# Craft.net
KiCad netlist of a schematic drawn in EAGLE
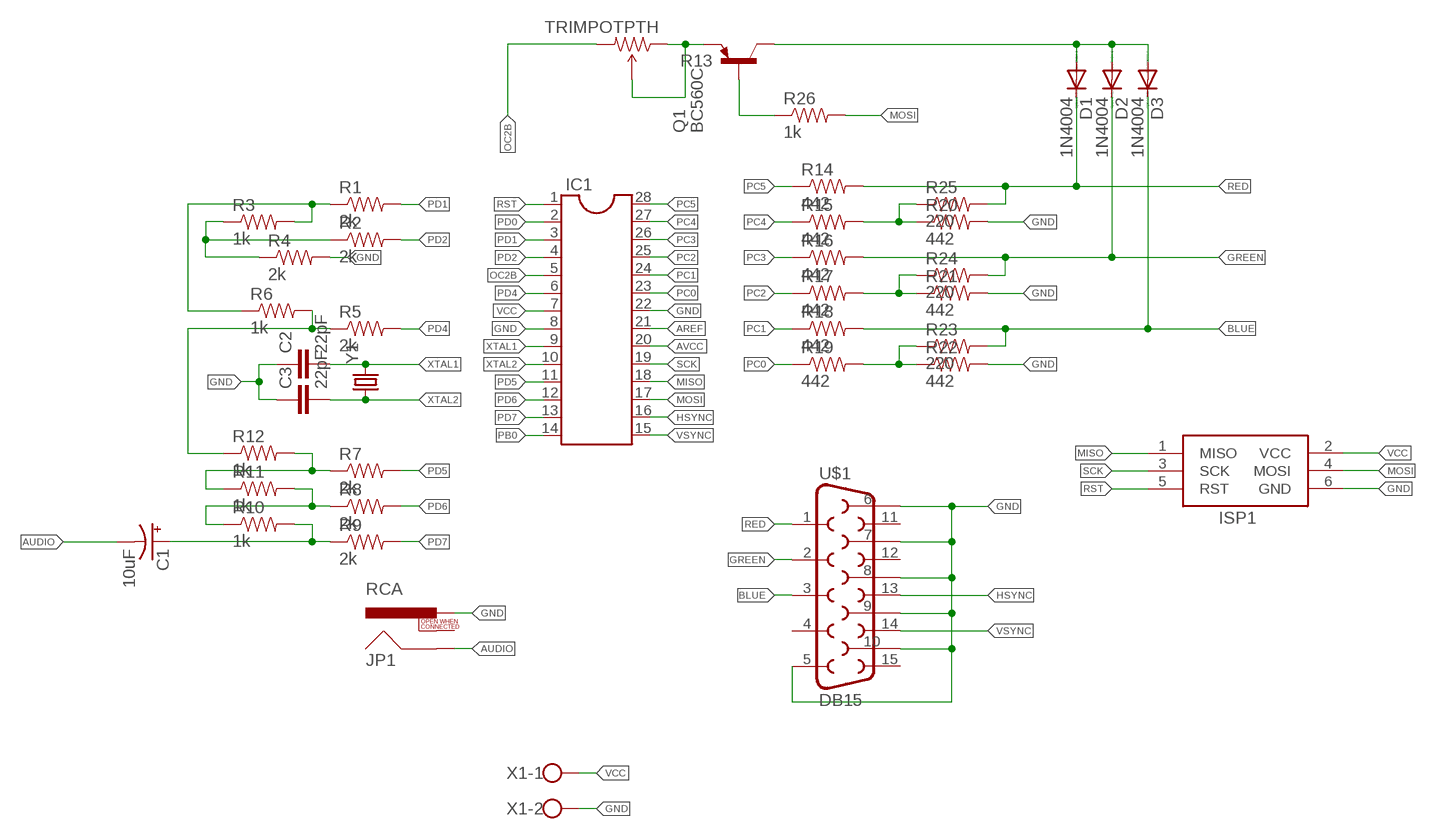
[diagram p0: schematic, sheet 1]

(export (version "E")
  (design (tool "Eeschema 10.0.6"))
  (components
    (comp (ref "C1")
      (value "10uF")
      (footprint "eagle-import:CPOL-RADIAL-100UF-25V")
      (libsource (lib "eagle-import") (part "CAP_POLPTH1"))
    )
    (comp (ref "C2")
      (value "22pF")
      (footprint "eagle-import:CAP-PTH-SMALLEZ")
      (libsource (lib "eagle-import") (part "CAPEZ"))
    )
    (comp (ref "C3")
      (value "22pF")
      (footprint "eagle-import:CAP-PTH-SMALLEZ")
      (libsource (lib "eagle-import") (part "CAPEZ"))
    )
    (comp (ref "D1")
      (value "1N4004")
      (footprint "eagle-import:DO41-10")
      (libsource (lib "eagle-import") (part "1N4004"))
    )
    (comp (ref "D2")
      (value "1N4004")
      (footprint "eagle-import:DO41-10")
      (libsource (lib "eagle-import") (part "1N4004"))
    )
    (comp (ref "D3")
      (value "1N4004")
      (footprint "eagle-import:DO41-10")
      (libsource (lib "eagle-import") (part "1N4004"))
    )
    (comp (ref "IC1")
      (value "DIL28-3")
      (footprint "eagle-import:DIL28-3")
      (libsource (lib "eagle-import") (part "DIL28-3"))
    )
    (comp (ref "ISP1")
      (value "AVRISP-6")
      (footprint "eagle-import:AVRISP")
      (libsource (lib "eagle-import") (part "AVRISP-6"))
    )
    (comp (ref "JP1")
      (value "RCA")
      (footprint "eagle-import:RCA")
      (libsource (lib "eagle-import") (part "RCA"))
    )
    (comp (ref "Q1")
      (value "BC560C")
      (footprint "eagle-import:TO92-EBC")
      (libsource (lib "eagle-import") (part "BC560C"))
    )
    (comp (ref "R1")
      (value "2k")
      (footprint "eagle-import:AXIAL-0.4")
      (libsource (lib "eagle-import") (part "RESISTORPTH-1/4W"))
    )
    (comp (ref "R2")
      (value "2k")
      (footprint "eagle-import:AXIAL-0.4")
      (libsource (lib "eagle-import") (part "RESISTORPTH-1/4W"))
    )
    (comp (ref "R3")
      (value "1k")
      (footprint "eagle-import:AXIAL-0.4")
      (libsource (lib "eagle-import") (part "RESISTORPTH-1/4W"))
    )
    (comp (ref "R4")
      (value "2k")
      (footprint "eagle-import:AXIAL-0.4")
      (libsource (lib "eagle-import") (part "RESISTORPTH-1/4W"))
    )
    (comp (ref "R5")
      (value "2k")
      (footprint "eagle-import:AXIAL-0.4")
      (libsource (lib "eagle-import") (part "RESISTORPTH-1/4W"))
    )
    (comp (ref "R6")
      (value "1k")
      (footprint "eagle-import:AXIAL-0.4")
      (libsource (lib "eagle-import") (part "RESISTORPTH-1/4W"))
    )
    (comp (ref "R7")
      (value "2k")
      (footprint "eagle-import:AXIAL-0.4")
      (libsource (lib "eagle-import") (part "RESISTORPTH-1/4W"))
    )
    (comp (ref "R8")
      (value "2k")
      (footprint "eagle-import:AXIAL-0.4")
      (libsource (lib "eagle-import") (part "RESISTORPTH-1/4W"))
    )
    (comp (ref "R9")
      (value "2k")
      (footprint "eagle-import:AXIAL-0.4")
      (libsource (lib "eagle-import") (part "RESISTORPTH-1/4W"))
    )
    (comp (ref "R10")
      (value "1k")
      (footprint "eagle-import:AXIAL-0.4")
      (libsource (lib "eagle-import") (part "RESISTORPTH-1/4W"))
    )
    (comp (ref "R11")
      (value "1k")
      (footprint "eagle-import:AXIAL-0.4")
      (libsource (lib "eagle-import") (part "RESISTORPTH-1/4W"))
    )
    (comp (ref "R12")
      (value "1k")
      (footprint "eagle-import:AXIAL-0.4")
      (libsource (lib "eagle-import") (part "RESISTORPTH-1/4W"))
    )
    (comp (ref "R13")
      (value "TRIMPOTPTH")
      (footprint "eagle-import:TRIM_POT_PTH")
      (libsource (lib "eagle-import") (part "TRIMPOTPTH"))
    )
    (comp (ref "R14")
      (value "442")
      (footprint "eagle-import:AXIAL-0.4")
      (libsource (lib "eagle-import") (part "RESISTORPTH-1/4W"))
    )
    (comp (ref "R15")
      (value "442")
      (footprint "eagle-import:AXIAL-0.4")
      (libsource (lib "eagle-import") (part "RESISTORPTH-1/4W"))
    )
    (comp (ref "R16")
      (value "442")
      (footprint "eagle-import:AXIAL-0.4")
      (libsource (lib "eagle-import") (part "RESISTORPTH-1/4W"))
    )
    (comp (ref "R17")
      (value "442")
      (footprint "eagle-import:AXIAL-0.4")
      (libsource (lib "eagle-import") (part "RESISTORPTH-1/4W"))
    )
    (comp (ref "R18")
      (value "442")
      (footprint "eagle-import:AXIAL-0.4")
      (libsource (lib "eagle-import") (part "RESISTORPTH-1/4W"))
    )
    (comp (ref "R19")
      (value "442")
      (footprint "eagle-import:AXIAL-0.4")
      (libsource (lib "eagle-import") (part "RESISTORPTH-1/4W"))
    )
    (comp (ref "R20")
      (value "442")
      (footprint "eagle-import:AXIAL-0.4")
      (libsource (lib "eagle-import") (part "RESISTORPTH-1/4W"))
    )
    (comp (ref "R21")
      (value "442")
      (footprint "eagle-import:AXIAL-0.4")
      (libsource (lib "eagle-import") (part "RESISTORPTH-1/4W"))
    )
    (comp (ref "R22")
      (value "442")
      (footprint "eagle-import:AXIAL-0.4")
      (libsource (lib "eagle-import") (part "RESISTORPTH-1/4W"))
    )
    (comp (ref "R23")
      (value "220")
      (footprint "eagle-import:AXIAL-0.4")
      (libsource (lib "eagle-import") (part "RESISTORPTH-1/4W"))
    )
    (comp (ref "R24")
      (value "220")
      (footprint "eagle-import:AXIAL-0.4")
      (libsource (lib "eagle-import") (part "RESISTORPTH-1/4W"))
    )
    (comp (ref "R25")
      (value "220")
      (footprint "eagle-import:AXIAL-0.4")
      (libsource (lib "eagle-import") (part "RESISTORPTH-1/4W"))
    )
    (comp (ref "R26")
      (value "1k")
      (footprint "eagle-import:AXIAL-0.4")
      (libsource (lib "eagle-import") (part "RESISTORPTH-1/4W"))
    )
    (comp (ref "U$1")
      (value "DB15")
      (footprint "eagle-import:DB15")
      (libsource (lib "eagle-import") (part "DB15"))
    )
    (comp (ref "X1")
      (value "W237-102")
      (footprint "eagle-import:W237-102")
      (fields (field (name "MPN") "237-102"))
      (libsource (lib "eagle-import") (part "W237-102"))
    )
    (comp (ref "Y1")
      (value "CRYSTALHC49UV")
      (footprint "eagle-import:HC49U-V")
      (libsource (lib "eagle-import") (part "CRYSTALHC49UV"))
    )
  )
  (nets
    (net (code "1") (name "AREF") (class "Default")
      (node (ref "IC1") (pin "21") (pinfunction "21_21") (pintype "passive"))
    )
    (net (code "2") (name "AUDIO") (class "Default")
      (node (ref "C1") (pin "2") (pinfunction "-_2") (pintype "passive"))
      (node (ref "JP1") (pin "SHELL") (pinfunction "SHELL_SHELL") (pintype "bidirectional"))
    )
    (net (code "3") (name "AVCC") (class "Default")
      (node (ref "IC1") (pin "20") (pinfunction "20_20") (pintype "passive"))
    )
    (net (code "4") (name "BLUE") (class "Default")
      (node (ref "D3") (pin "C") (pinfunction "C_C") (pintype "passive"))
      (node (ref "R18") (pin "P$2") (pinfunction "2_P$2") (pintype "passive"))
      (node (ref "R23") (pin "P$2") (pinfunction "2_P$2") (pintype "passive"))
      (node (ref "U$1") (pin "3") (pinfunction "3_3") (pintype "passive"))
    )
    (net (code "5") (name "GND") (class "Default")
      (node (ref "C2") (pin "1") (pinfunction "1_1") (pintype "passive"))
      (node (ref "C3") (pin "1") (pinfunction "1_1") (pintype "passive"))
      (node (ref "IC1") (pin "22") (pinfunction "22_22") (pintype "passive"))
      (node (ref "IC1") (pin "8") (pinfunction "8_8") (pintype "passive"))
      (node (ref "ISP1") (pin "6") (pinfunction "GND_6") (pintype "power_in"))
      (node (ref "JP1") (pin "PIN") (pinfunction "PIN_PIN") (pintype "bidirectional"))
      (node (ref "R20") (pin "P$2") (pinfunction "2_P$2") (pintype "passive"))
      (node (ref "R21") (pin "P$2") (pinfunction "2_P$2") (pintype "passive"))
      (node (ref "R22") (pin "P$2") (pinfunction "2_P$2") (pintype "passive"))
      (node (ref "R4") (pin "P$2") (pinfunction "2_P$2") (pintype "passive"))
      (node (ref "U$1") (pin "10") (pinfunction "10_10") (pintype "passive"))
      (node (ref "U$1") (pin "5") (pinfunction "5_5") (pintype "passive"))
      (node (ref "U$1") (pin "6") (pinfunction "6_6") (pintype "passive"))
      (node (ref "U$1") (pin "7") (pinfunction "7_7") (pintype "passive"))
      (node (ref "U$1") (pin "8") (pinfunction "8_8") (pintype "passive"))
      (node (ref "U$1") (pin "9") (pinfunction "9_9") (pintype "passive"))
      (node (ref "X1") (pin "2") (pinfunction "KL_2") (pintype "passive"))
    )
    (net (code "6") (name "GREEN") (class "Default")
      (node (ref "D2") (pin "C") (pinfunction "C_C") (pintype "passive"))
      (node (ref "R16") (pin "P$2") (pinfunction "2_P$2") (pintype "passive"))
      (node (ref "R24") (pin "P$2") (pinfunction "2_P$2") (pintype "passive"))
      (node (ref "U$1") (pin "2") (pinfunction "2_2") (pintype "passive"))
    )
    (net (code "7") (name "HSYNC") (class "Default")
      (node (ref "IC1") (pin "16") (pinfunction "16_16") (pintype "passive"))
      (node (ref "U$1") (pin "13") (pinfunction "13_13") (pintype "passive"))
    )
    (net (code "8") (name "MISO") (class "Default")
      (node (ref "IC1") (pin "18") (pinfunction "18_18") (pintype "passive"))
      (node (ref "ISP1") (pin "1") (pinfunction "MISO_1") (pintype "input"))
    )
    (net (code "9") (name "MOSI") (class "Default")
      (node (ref "IC1") (pin "17") (pinfunction "17_17") (pintype "passive"))
      (node (ref "ISP1") (pin "4") (pinfunction "MOSI_4") (pintype "output"))
      (node (ref "R26") (pin "P$2") (pinfunction "2_P$2") (pintype "passive"))
    )
    (net (code "10") (name "Net-(C1-+)") (class "Default")
      (node (ref "C1") (pin "1") (pinfunction "+_1") (pintype "passive"))
      (node (ref "R10") (pin "P$2") (pinfunction "2_P$2") (pintype "passive"))
      (node (ref "R9") (pin "P$1") (pinfunction "1_P$1") (pintype "passive"))
    )
    (net (code "11") (name "Net-(D1-PadA)") (class "Default")
      (node (ref "D1") (pin "A") (pinfunction "A_A") (pintype "passive"))
      (node (ref "D2") (pin "A") (pinfunction "A_A") (pintype "passive"))
      (node (ref "D3") (pin "A") (pinfunction "A_A") (pintype "passive"))
      (node (ref "Q1") (pin "C") (pinfunction "C_C") (pintype "passive"))
    )
    (net (code "12") (name "Net-(R1-1)") (class "Default")
      (node (ref "R1") (pin "P$1") (pinfunction "1_P$1") (pintype "passive"))
      (node (ref "R3") (pin "P$2") (pinfunction "2_P$2") (pintype "passive"))
      (node (ref "R6") (pin "P$1") (pinfunction "1_P$1") (pintype "passive"))
    )
    (net (code "13") (name "Net-(R2-1)") (class "Default")
      (node (ref "R2") (pin "P$1") (pinfunction "1_P$1") (pintype "passive"))
      (node (ref "R3") (pin "P$1") (pinfunction "1_P$1") (pintype "passive"))
      (node (ref "R4") (pin "P$1") (pinfunction "1_P$1") (pintype "passive"))
    )
    (net (code "14") (name "Net-(R10-1)") (class "Default")
      (node (ref "R10") (pin "P$1") (pinfunction "1_P$1") (pintype "passive"))
      (node (ref "R11") (pin "P$2") (pinfunction "2_P$2") (pintype "passive"))
      (node (ref "R8") (pin "P$1") (pinfunction "1_P$1") (pintype "passive"))
    )
    (net (code "15") (name "Net-(R11-1)") (class "Default")
      (node (ref "R11") (pin "P$1") (pinfunction "1_P$1") (pintype "passive"))
      (node (ref "R12") (pin "P$2") (pinfunction "2_P$2") (pintype "passive"))
      (node (ref "R7") (pin "P$1") (pinfunction "1_P$1") (pintype "passive"))
    )
    (net (code "16") (name "Net-(R12-1)") (class "Default")
      (node (ref "R12") (pin "P$1") (pinfunction "1_P$1") (pintype "passive"))
      (node (ref "R5") (pin "P$1") (pinfunction "1_P$1") (pintype "passive"))
      (node (ref "R6") (pin "P$2") (pinfunction "2_P$2") (pintype "passive"))
    )
    (net (code "17") (name "Net-(R13-CCW)") (class "Default")
      (node (ref "Q1") (pin "E") (pinfunction "E_E") (pintype "passive"))
      (node (ref "R13") (pin "1") (pinfunction "CCW_1") (pintype "passive"))
      (node (ref "R13") (pin "2") (pinfunction "WIPER_2") (pintype "passive"))
    )
    (net (code "18") (name "Net-(R15-2)") (class "Default")
      (node (ref "R15") (pin "P$2") (pinfunction "2_P$2") (pintype "passive"))
      (node (ref "R20") (pin "P$1") (pinfunction "1_P$1") (pintype "passive"))
      (node (ref "R25") (pin "P$1") (pinfunction "1_P$1") (pintype "passive"))
    )
    (net (code "19") (name "Net-(R17-2)") (class "Default")
      (node (ref "R17") (pin "P$2") (pinfunction "2_P$2") (pintype "passive"))
      (node (ref "R21") (pin "P$1") (pinfunction "1_P$1") (pintype "passive"))
      (node (ref "R24") (pin "P$1") (pinfunction "1_P$1") (pintype "passive"))
    )
    (net (code "20") (name "Net-(R19-2)") (class "Default")
      (node (ref "R19") (pin "P$2") (pinfunction "2_P$2") (pintype "passive"))
      (node (ref "R22") (pin "P$1") (pinfunction "1_P$1") (pintype "passive"))
      (node (ref "R23") (pin "P$1") (pinfunction "1_P$1") (pintype "passive"))
    )
    (net (code "21") (name "Net-(R26-1)") (class "Default")
      (node (ref "Q1") (pin "B") (pinfunction "B_B") (pintype "passive"))
      (node (ref "R26") (pin "P$1") (pinfunction "1_P$1") (pintype "passive"))
    )
    (net (code "22") (name "OC2B") (class "Default")
      (node (ref "IC1") (pin "5") (pinfunction "5_5") (pintype "passive"))
      (node (ref "R13") (pin "3") (pinfunction "CW_3") (pintype "passive"))
    )
    (net (code "23") (name "PB0") (class "Default")
      (node (ref "IC1") (pin "14") (pinfunction "14_14") (pintype "passive"))
    )
    (net (code "24") (name "PC0") (class "Default")
      (node (ref "IC1") (pin "23") (pinfunction "23_23") (pintype "passive"))
      (node (ref "R19") (pin "P$1") (pinfunction "1_P$1") (pintype "passive"))
    )
    (net (code "25") (name "PC1") (class "Default")
      (node (ref "IC1") (pin "24") (pinfunction "24_24") (pintype "passive"))
      (node (ref "R18") (pin "P$1") (pinfunction "1_P$1") (pintype "passive"))
    )
    (net (code "26") (name "PC2") (class "Default")
      (node (ref "IC1") (pin "25") (pinfunction "25_25") (pintype "passive"))
      (node (ref "R17") (pin "P$1") (pinfunction "1_P$1") (pintype "passive"))
    )
    (net (code "27") (name "PC3") (class "Default")
      (node (ref "IC1") (pin "26") (pinfunction "26_26") (pintype "passive"))
      (node (ref "R16") (pin "P$1") (pinfunction "1_P$1") (pintype "passive"))
    )
    (net (code "28") (name "PC4") (class "Default")
      (node (ref "IC1") (pin "27") (pinfunction "27_27") (pintype "passive"))
      (node (ref "R15") (pin "P$1") (pinfunction "1_P$1") (pintype "passive"))
    )
    (net (code "29") (name "PC5") (class "Default")
      (node (ref "IC1") (pin "28") (pinfunction "28_28") (pintype "passive"))
      (node (ref "R14") (pin "P$1") (pinfunction "1_P$1") (pintype "passive"))
    )
    (net (code "30") (name "PD0") (class "Default")
      (node (ref "IC1") (pin "2") (pinfunction "2_2") (pintype "passive"))
    )
    (net (code "31") (name "PD1") (class "Default")
      (node (ref "IC1") (pin "3") (pinfunction "3_3") (pintype "passive"))
      (node (ref "R1") (pin "P$2") (pinfunction "2_P$2") (pintype "passive"))
    )
    (net (code "32") (name "PD2") (class "Default")
      (node (ref "IC1") (pin "4") (pinfunction "4_4") (pintype "passive"))
      (node (ref "R2") (pin "P$2") (pinfunction "2_P$2") (pintype "passive"))
    )
    (net (code "33") (name "PD4") (class "Default")
      (node (ref "IC1") (pin "6") (pinfunction "6_6") (pintype "passive"))
      (node (ref "R5") (pin "P$2") (pinfunction "2_P$2") (pintype "passive"))
    )
    (net (code "34") (name "PD5") (class "Default")
      (node (ref "IC1") (pin "11") (pinfunction "11_11") (pintype "passive"))
      (node (ref "R7") (pin "P$2") (pinfunction "2_P$2") (pintype "passive"))
    )
    (net (code "35") (name "PD6") (class "Default")
      (node (ref "IC1") (pin "12") (pinfunction "12_12") (pintype "passive"))
      (node (ref "R8") (pin "P$2") (pinfunction "2_P$2") (pintype "passive"))
    )
    (net (code "36") (name "PD7") (class "Default")
      (node (ref "IC1") (pin "13") (pinfunction "13_13") (pintype "passive"))
      (node (ref "R9") (pin "P$2") (pinfunction "2_P$2") (pintype "passive"))
    )
    (net (code "37") (name "RED") (class "Default")
      (node (ref "D1") (pin "C") (pinfunction "C_C") (pintype "passive"))
      (node (ref "R14") (pin "P$2") (pinfunction "2_P$2") (pintype "passive"))
      (node (ref "R25") (pin "P$2") (pinfunction "2_P$2") (pintype "passive"))
      (node (ref "U$1") (pin "1") (pinfunction "1_1") (pintype "passive"))
    )
    (net (code "38") (name "RST") (class "Default")
      (node (ref "IC1") (pin "1") (pinfunction "1_1") (pintype "passive"))
      (node (ref "ISP1") (pin "5") (pinfunction "RST_5") (pintype "output"))
    )
    (net (code "39") (name "SCK") (class "Default")
      (node (ref "IC1") (pin "19") (pinfunction "19_19") (pintype "passive"))
      (node (ref "ISP1") (pin "3") (pinfunction "SCK_3") (pintype "output"))
    )
    (net (code "40") (name "VCC") (class "Default")
      (node (ref "IC1") (pin "7") (pinfunction "7_7") (pintype "passive"))
      (node (ref "ISP1") (pin "2") (pinfunction "VCC_2") (pintype "power_in"))
      (node (ref "X1") (pin "1") (pinfunction "KL_1") (pintype "passive"))
    )
    (net (code "41") (name "VSYNC") (class "Default")
      (node (ref "IC1") (pin "15") (pinfunction "15_15") (pintype "passive"))
      (node (ref "U$1") (pin "14") (pinfunction "14_14") (pintype "passive"))
    )
    (net (code "42") (name "XTAL1") (class "Default")
      (node (ref "C2") (pin "2") (pinfunction "2_2") (pintype "passive"))
      (node (ref "IC1") (pin "9") (pinfunction "9_9") (pintype "passive"))
      (node (ref "Y1") (pin "2") (pinfunction "2_2") (pintype "passive"))
    )
    (net (code "43") (name "XTAL2") (class "Default")
      (node (ref "C3") (pin "2") (pinfunction "2_2") (pintype "passive"))
      (node (ref "IC1") (pin "10") (pinfunction "10_10") (pintype "passive"))
      (node (ref "Y1") (pin "1") (pinfunction "1_1") (pintype "passive"))
    )
    (net (code "44") (name "unconnected-(JP1-PadSWITCH)") (class "Default")
      (node (ref "JP1") (pin "SWITCH") (pinfunction "SWITCH_SWITCH") (pintype "bidirectional"))
    )
    (net (code "45") (name "unconnected-(U$1-Pad4)") (class "Default")
      (node (ref "U$1") (pin "4") (pinfunction "4_4") (pintype "passive"))
    )
    (net (code "46") (name "unconnected-(U$1-Pad11)") (class "Default")
      (node (ref "U$1") (pin "11") (pinfunction "11_11") (pintype "passive"))
    )
    (net (code "47") (name "unconnected-(U$1-Pad12)") (class "Default")
      (node (ref "U$1") (pin "12") (pinfunction "12_12") (pintype "passive"))
    )
    (net (code "48") (name "unconnected-(U$1-Pad15)") (class "Default")
      (node (ref "U$1") (pin "15") (pinfunction "15_15") (pintype "passive"))
    )
  )
)
